# ME433_sunyue.net
KiCad netlist of a schematic drawn in EAGLE
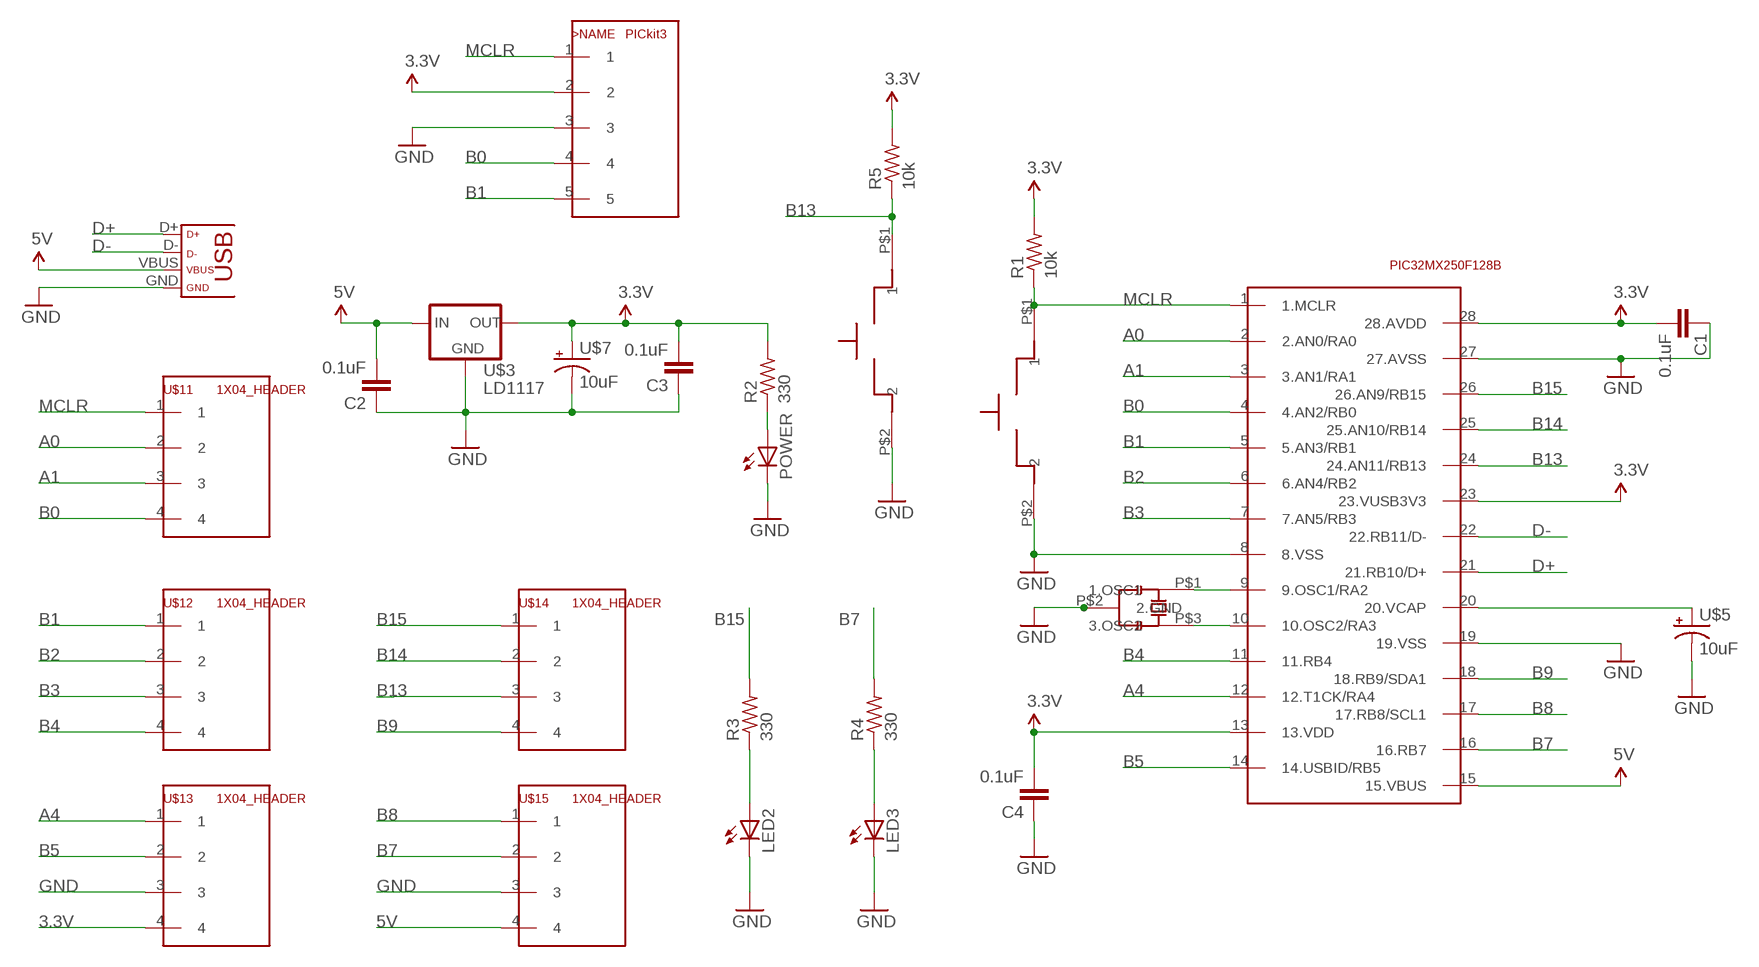
[diagram p0: schematic, sheet 1]

(export (version "E")
  (design (tool "Eeschema 10.0.6"))
  (components
    (comp (ref ">NAME")
      (value "PICkit3")
      (footprint "eagle-import:1X05")
      (libsource (lib "eagle-import") (part "1X05_HEADER"))
    )
    (comp (ref "C1")
      (value "0.1uF")
      (footprint "eagle-import:C025-025X050")
      (libsource (lib "eagle-import") (part "C-EU025-025X050"))
    )
    (comp (ref "C2")
      (value "0.1uF")
      (footprint "eagle-import:C025-025X050")
      (libsource (lib "eagle-import") (part "C-EU025-025X050"))
    )
    (comp (ref "C3")
      (value "0.1uF")
      (footprint "eagle-import:C025-025X050")
      (libsource (lib "eagle-import") (part "C-EU025-025X050"))
    )
    (comp (ref "C4")
      (value "0.1uF")
      (footprint "eagle-import:C025-025X050")
      (libsource (lib "eagle-import") (part "C-EU025-025X050"))
    )
    (comp (ref "LED2")
      (value "LED3MM")
      (footprint "eagle-import:LED3MM")
      (libsource (lib "eagle-import") (part "LED3MM"))
    )
    (comp (ref "LED3")
      (value "LED3MM")
      (footprint "eagle-import:LED3MM")
      (libsource (lib "eagle-import") (part "LED3MM"))
    )
    (comp (ref "POWER")
      (value "LED3MM")
      (footprint "eagle-import:LED3MM")
      (libsource (lib "eagle-import") (part "LED3MM"))
    )
    (comp (ref "R1")
      (value "10k")
      (footprint "eagle-import:0207_10")
      (libsource (lib "eagle-import") (part "R-US_0207/10"))
    )
    (comp (ref "R2")
      (value "330")
      (footprint "eagle-import:0207_10")
      (libsource (lib "eagle-import") (part "R-US_0207/10"))
    )
    (comp (ref "R3")
      (value "330")
      (footprint "eagle-import:0207_10")
      (libsource (lib "eagle-import") (part "R-US_0207/10"))
    )
    (comp (ref "R4")
      (value "330")
      (footprint "eagle-import:0207_10")
      (libsource (lib "eagle-import") (part "R-US_0207/10"))
    )
    (comp (ref "R5")
      (value "10k")
      (footprint "eagle-import:0207_10")
      (libsource (lib "eagle-import") (part "R-US_0207/10"))
    )
    (comp (ref "RESET")
      (value "RESET")
      (footprint "eagle-import:BUTTON")
      (libsource (lib "eagle-import") (part "BUTTON"))
    )
    (comp (ref "U$1")
      (value "PIC32MX250F128B")
      (footprint "eagle-import:DIL28-3")
      (libsource (lib "eagle-import") (part "PIC32MX250F128B"))
    )
    (comp (ref "U$2")
      (value "CRYSTAL")
      (footprint "eagle-import:CRYSTAL")
      (libsource (lib "eagle-import") (part "CRYSTAL"))
    )
    (comp (ref "U$3")
      (value "LD1117")
      (footprint "eagle-import:TO220")
      (libsource (lib "eagle-import") (part "LD1117"))
    )
    (comp (ref "U$5")
      (value "10uF")
      (footprint "eagle-import:CAP_POL_D")
      (libsource (lib "eagle-import") (part "CAP_POL"))
    )
    (comp (ref "U$7")
      (value "10uF")
      (footprint "eagle-import:CAP_POL_D")
      (libsource (lib "eagle-import") (part "CAP_POL"))
    )
    (comp (ref "U$9")
      (value "USB")
      (footprint "eagle-import:USB-MINIB")
      (libsource (lib "eagle-import") (part "USB"))
    )
    (comp (ref "U$11")
      (value "1X04_HEADER")
      (footprint "eagle-import:1X04")
      (libsource (lib "eagle-import") (part "1X04_HEADER"))
    )
    (comp (ref "U$12")
      (value "1X04_HEADER")
      (footprint "eagle-import:1X04")
      (libsource (lib "eagle-import") (part "1X04_HEADER"))
    )
    (comp (ref "U$13")
      (value "1X04_HEADER")
      (footprint "eagle-import:1X04")
      (libsource (lib "eagle-import") (part "1X04_HEADER"))
    )
    (comp (ref "U$14")
      (value "1X04_HEADER")
      (footprint "eagle-import:1X04")
      (libsource (lib "eagle-import") (part "1X04_HEADER"))
    )
    (comp (ref "U$15")
      (value "1X04_HEADER")
      (footprint "eagle-import:1X04")
      (libsource (lib "eagle-import") (part "1X04_HEADER"))
    )
    (comp (ref "USER")
      (value "BUTTON")
      (footprint "eagle-import:BUTTON")
      (libsource (lib "eagle-import") (part "BUTTON"))
    )
  )
  (nets
    (net (code "1") (name "/A0") (class "Default")
      (node (ref "U$1") (pin "2") (pinfunction "2.AN0/RA0_2") (pintype "bidirectional"))
      (node (ref "U$11") (pin "2") (pinfunction "2_2") (pintype "bidirectional"))
    )
    (net (code "2") (name "/A1") (class "Default")
      (node (ref "U$1") (pin "3") (pinfunction "3.AN1/RA1_3") (pintype "bidirectional"))
      (node (ref "U$11") (pin "3") (pinfunction "3_3") (pintype "bidirectional"))
    )
    (net (code "3") (name "/A4") (class "Default")
      (node (ref "U$1") (pin "12") (pinfunction "12.T1CK/RA4_12") (pintype "bidirectional"))
      (node (ref "U$13") (pin "1") (pinfunction "1_1") (pintype "bidirectional"))
    )
    (net (code "4") (name "/B0") (class "Default")
      (node (ref ">NAME") (pin "4") (pinfunction "4_4") (pintype "bidirectional"))
      (node (ref "U$1") (pin "4") (pinfunction "4.AN2/RB0_4") (pintype "bidirectional"))
      (node (ref "U$11") (pin "4") (pinfunction "4_4") (pintype "bidirectional"))
    )
    (net (code "5") (name "/B1") (class "Default")
      (node (ref ">NAME") (pin "5") (pinfunction "5_5") (pintype "bidirectional"))
      (node (ref "U$1") (pin "5") (pinfunction "5.AN3/RB1_5") (pintype "bidirectional"))
      (node (ref "U$12") (pin "1") (pinfunction "1_1") (pintype "bidirectional"))
    )
    (net (code "6") (name "/B2") (class "Default")
      (node (ref "U$1") (pin "6") (pinfunction "6.AN4/RB2_6") (pintype "bidirectional"))
      (node (ref "U$12") (pin "2") (pinfunction "2_2") (pintype "bidirectional"))
    )
    (net (code "7") (name "/B3") (class "Default")
      (node (ref "U$1") (pin "7") (pinfunction "7.AN5/RB3_7") (pintype "bidirectional"))
      (node (ref "U$12") (pin "3") (pinfunction "3_3") (pintype "bidirectional"))
    )
    (net (code "8") (name "/B4") (class "Default")
      (node (ref "U$1") (pin "11") (pinfunction "11.RB4_11") (pintype "bidirectional"))
      (node (ref "U$12") (pin "4") (pinfunction "4_4") (pintype "bidirectional"))
    )
    (net (code "9") (name "/B5") (class "Default")
      (node (ref "U$1") (pin "14") (pinfunction "14.USBID/RB5_14") (pintype "bidirectional"))
      (node (ref "U$13") (pin "2") (pinfunction "2_2") (pintype "bidirectional"))
    )
    (net (code "10") (name "/B7") (class "Default")
      (node (ref "R4") (pin "2") (pinfunction "2_2") (pintype "passive"))
      (node (ref "U$1") (pin "16") (pinfunction "16.RB7_16") (pintype "bidirectional"))
      (node (ref "U$15") (pin "2") (pinfunction "2_2") (pintype "bidirectional"))
    )
    (net (code "11") (name "/B8") (class "Default")
      (node (ref "U$1") (pin "17") (pinfunction "17.RB8/SCL1_17") (pintype "bidirectional"))
      (node (ref "U$15") (pin "1") (pinfunction "1_1") (pintype "bidirectional"))
    )
    (net (code "12") (name "/B9") (class "Default")
      (node (ref "U$1") (pin "18") (pinfunction "18.RB9/SDA1_18") (pintype "bidirectional"))
      (node (ref "U$14") (pin "4") (pinfunction "4_4") (pintype "bidirectional"))
    )
    (net (code "13") (name "/B13") (class "Default")
      (node (ref "R5") (pin "1") (pinfunction "1_1") (pintype "passive"))
      (node (ref "U$1") (pin "24") (pinfunction "24.AN11/RB13_24") (pintype "bidirectional"))
      (node (ref "U$14") (pin "3") (pinfunction "3_3") (pintype "bidirectional"))
      (node (ref "USER") (pin "P$1") (pinfunction "1_P$1") (pintype "bidirectional"))
    )
    (net (code "14") (name "/B14") (class "Default")
      (node (ref "U$1") (pin "25") (pinfunction "25.AN10/RB14_25") (pintype "bidirectional"))
      (node (ref "U$14") (pin "2") (pinfunction "2_2") (pintype "bidirectional"))
    )
    (net (code "15") (name "/B15") (class "Default")
      (node (ref "R3") (pin "2") (pinfunction "2_2") (pintype "passive"))
      (node (ref "U$1") (pin "26") (pinfunction "26.AN9/RB15_26") (pintype "bidirectional"))
      (node (ref "U$14") (pin "1") (pinfunction "1_1") (pintype "bidirectional"))
    )
    (net (code "16") (name "/D+") (class "Default")
      (node (ref "U$1") (pin "21") (pinfunction "21.RB10/D+_21") (pintype "bidirectional"))
      (node (ref "U$9") (pin "D+") (pinfunction "D+_D+") (pintype "bidirectional"))
    )
    (net (code "17") (name "/D-") (class "Default")
      (node (ref "U$1") (pin "22") (pinfunction "22.RB11/D-_22") (pintype "bidirectional"))
      (node (ref "U$9") (pin "D-") (pinfunction "D-_D-") (pintype "bidirectional"))
    )
    (net (code "18") (name "/MCLR") (class "Default")
      (node (ref ">NAME") (pin "1") (pinfunction "1_1") (pintype "bidirectional"))
      (node (ref "R1") (pin "1") (pinfunction "1_1") (pintype "passive"))
      (node (ref "RESET") (pin "P$1") (pinfunction "1_P$1") (pintype "bidirectional"))
      (node (ref "U$1") (pin "1") (pinfunction "1.MCLR_1") (pintype "bidirectional"))
      (node (ref "U$11") (pin "1") (pinfunction "1_1") (pintype "bidirectional"))
    )
    (net (code "19") (name "3.3V") (class "Default")
      (node (ref ">NAME") (pin "2") (pinfunction "2_2") (pintype "bidirectional"))
      (node (ref "C1") (pin "2") (pinfunction "2_2") (pintype "passive"))
      (node (ref "C3") (pin "2") (pinfunction "2_2") (pintype "passive"))
      (node (ref "C4") (pin "2") (pinfunction "2_2") (pintype "passive"))
      (node (ref "R1") (pin "2") (pinfunction "2_2") (pintype "passive"))
      (node (ref "R2") (pin "2") (pinfunction "2_2") (pintype "passive"))
      (node (ref "R5") (pin "2") (pinfunction "2_2") (pintype "passive"))
      (node (ref "U$1") (pin "13") (pinfunction "13.VDD_13") (pintype "bidirectional"))
      (node (ref "U$1") (pin "23") (pinfunction "23.VUSB3V3_23") (pintype "bidirectional"))
      (node (ref "U$1") (pin "28") (pinfunction "28.AVDD_28") (pintype "bidirectional"))
      (node (ref "U$13") (pin "4") (pinfunction "4_4") (pintype "bidirectional"))
      (node (ref "U$3") (pin "2") (pinfunction "OUT_2") (pintype "output"))
      (node (ref "U$7") (pin "1") (pinfunction "+_1") (pintype "passive"))
    )
    (net (code "20") (name "5V") (class "Default")
      (node (ref "C2") (pin "2") (pinfunction "2_2") (pintype "passive"))
      (node (ref "U$1") (pin "15") (pinfunction "15.VBUS_15") (pintype "bidirectional"))
      (node (ref "U$15") (pin "4") (pinfunction "4_4") (pintype "bidirectional"))
      (node (ref "U$3") (pin "3") (pinfunction "IN_3") (pintype "input"))
      (node (ref "U$9") (pin "VBUS") (pinfunction "VBUS_VBUS") (pintype "bidirectional"))
    )
    (net (code "21") (name "GND") (class "Default")
      (node (ref ">NAME") (pin "3") (pinfunction "3_3") (pintype "bidirectional"))
      (node (ref "C1") (pin "1") (pinfunction "1_1") (pintype "passive"))
      (node (ref "C2") (pin "1") (pinfunction "1_1") (pintype "passive"))
      (node (ref "C3") (pin "1") (pinfunction "1_1") (pintype "passive"))
      (node (ref "C4") (pin "1") (pinfunction "1_1") (pintype "passive"))
      (node (ref "LED2") (pin "K") (pinfunction "C_K") (pintype "passive"))
      (node (ref "LED3") (pin "K") (pinfunction "C_K") (pintype "passive"))
      (node (ref "POWER") (pin "K") (pinfunction "C_K") (pintype "passive"))
      (node (ref "RESET") (pin "P$2") (pinfunction "2_P$2") (pintype "bidirectional"))
      (node (ref "U$1") (pin "19") (pinfunction "19.VSS_19") (pintype "bidirectional"))
      (node (ref "U$1") (pin "27") (pinfunction "27.AVSS_27") (pintype "bidirectional"))
      (node (ref "U$1") (pin "8") (pinfunction "8.VSS_8") (pintype "bidirectional"))
      (node (ref "U$13") (pin "3") (pinfunction "3_3") (pintype "bidirectional"))
      (node (ref "U$15") (pin "3") (pinfunction "3_3") (pintype "bidirectional"))
      (node (ref "U$2") (pin "P$2") (pinfunction "2.GND_P$2") (pintype "bidirectional"))
      (node (ref "U$3") (pin "1") (pinfunction "GND_1") (pintype "input"))
      (node (ref "U$5") (pin "2") (pinfunction "-_2") (pintype "passive"))
      (node (ref "U$7") (pin "2") (pinfunction "-_2") (pintype "passive"))
      (node (ref "U$9") (pin "GND") (pinfunction "GND_GND") (pintype "bidirectional"))
      (node (ref "USER") (pin "P$2") (pinfunction "2_P$2") (pintype "bidirectional"))
    )
    (net (code "22") (name "Net-(LED2-PadA)") (class "Default")
      (node (ref "LED2") (pin "A") (pinfunction "A_A") (pintype "passive"))
      (node (ref "R3") (pin "1") (pinfunction "1_1") (pintype "passive"))
    )
    (net (code "23") (name "Net-(LED3-PadA)") (class "Default")
      (node (ref "LED3") (pin "A") (pinfunction "A_A") (pintype "passive"))
      (node (ref "R4") (pin "1") (pinfunction "1_1") (pintype "passive"))
    )
    (net (code "24") (name "Net-(POWER-PadA)") (class "Default")
      (node (ref "POWER") (pin "A") (pinfunction "A_A") (pintype "passive"))
      (node (ref "R2") (pin "1") (pinfunction "1_1") (pintype "passive"))
    )
    (net (code "25") (name "Net-(U$1-9.OSC1{slash}RA2)") (class "Default")
      (node (ref "U$1") (pin "9") (pinfunction "9.OSC1/RA2_9") (pintype "bidirectional"))
      (node (ref "U$2") (pin "P$1") (pinfunction "1.OSC1_P$1") (pintype "bidirectional"))
    )
    (net (code "26") (name "Net-(U$1-10.OSC2{slash}RA3)") (class "Default")
      (node (ref "U$1") (pin "10") (pinfunction "10.OSC2/RA3_10") (pintype "bidirectional"))
      (node (ref "U$2") (pin "P$3") (pinfunction "3.OSC2_P$3") (pintype "bidirectional"))
    )
    (net (code "27") (name "Net-(U$1-20.VCAP)") (class "Default")
      (node (ref "U$1") (pin "20") (pinfunction "20.VCAP_20") (pintype "bidirectional"))
      (node (ref "U$5") (pin "1") (pinfunction "+_1") (pintype "passive"))
    )
  )
)
